# LIDAR-Lite-Shield-ArduinoUNO-StepperVers.net
KiCad netlist of a schematic drawn in EAGLE
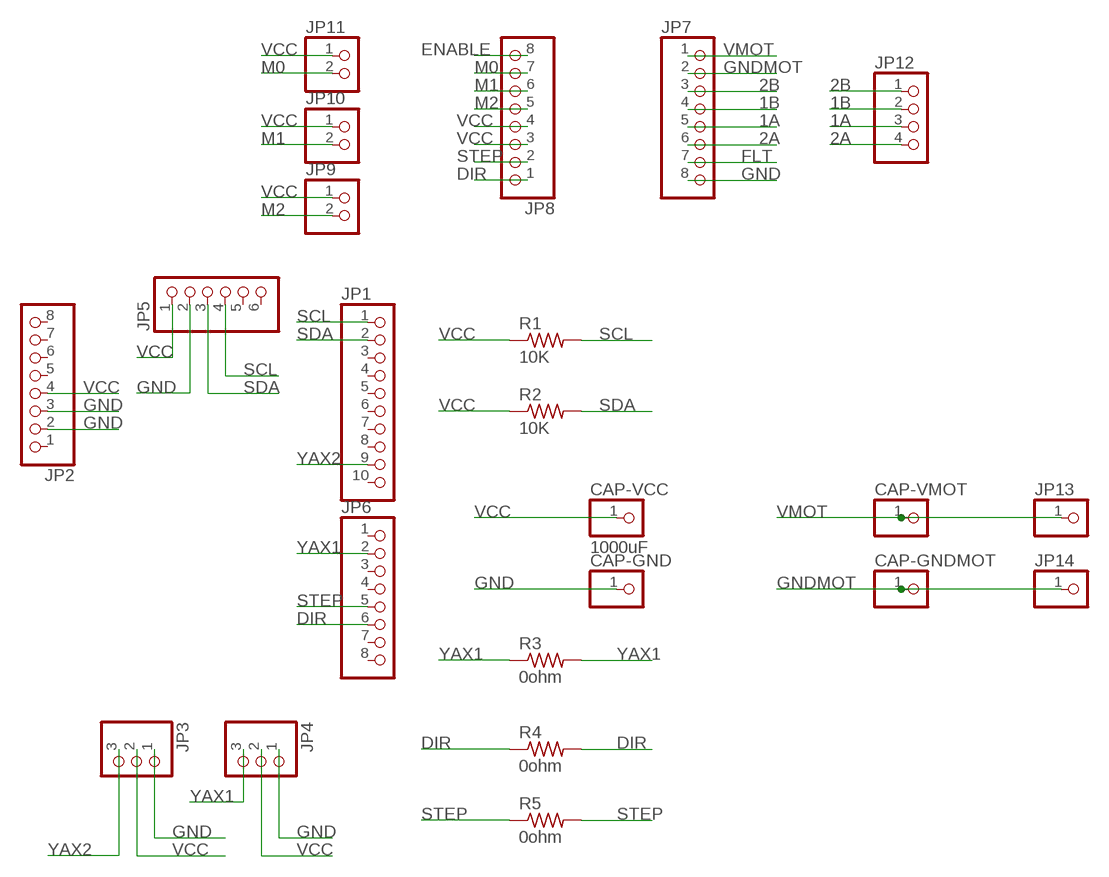
[diagram p0: schematic, sheet 1]

(export (version "E")
  (design (tool "Eeschema 10.0.6"))
  (components
    (comp (ref "CAP-GND")
      (value "PINHD-1X1")
      (footprint "eagle-import:1X01")
      (libsource (lib "eagle-import") (part "PINHD-1X1"))
    )
    (comp (ref "CAP-GNDMOT")
      (value "PINHD-1X1")
      (footprint "eagle-import:1X01")
      (libsource (lib "eagle-import") (part "PINHD-1X1"))
    )
    (comp (ref "CAP-VCC")
      (value "1000uF")
      (footprint "eagle-import:1X01")
      (libsource (lib "eagle-import") (part "PINHD-1X1"))
    )
    (comp (ref "CAP-VMOT")
      (value "PINHD-1X1")
      (footprint "eagle-import:1X01")
      (libsource (lib "eagle-import") (part "PINHD-1X1"))
    )
    (comp (ref "JP1")
      (value "PINHD-1X10")
      (footprint "eagle-import:1X10")
      (libsource (lib "eagle-import") (part "PINHD-1X10"))
    )
    (comp (ref "JP2")
      (value "PINHD-1X8")
      (footprint "eagle-import:1X08")
      (libsource (lib "eagle-import") (part "PINHD-1X8"))
    )
    (comp (ref "JP3")
      (value "PINHD-1X3")
      (footprint "eagle-import:1X03")
      (libsource (lib "eagle-import") (part "PINHD-1X3"))
    )
    (comp (ref "JP4")
      (value "PINHD-1X3")
      (footprint "eagle-import:1X03")
      (libsource (lib "eagle-import") (part "PINHD-1X3"))
    )
    (comp (ref "JP5")
      (value "PINHD-1X6")
      (footprint "eagle-import:1X06")
      (libsource (lib "eagle-import") (part "PINHD-1X6"))
    )
    (comp (ref "JP6")
      (value "PINHD-1X8")
      (footprint "eagle-import:1X08")
      (libsource (lib "eagle-import") (part "PINHD-1X8"))
    )
    (comp (ref "JP7")
      (value "PINHD-1X8")
      (footprint "eagle-import:1X08")
      (libsource (lib "eagle-import") (part "PINHD-1X8"))
    )
    (comp (ref "JP8")
      (value "PINHD-1X8")
      (footprint "eagle-import:1X08")
      (libsource (lib "eagle-import") (part "PINHD-1X8"))
    )
    (comp (ref "JP9")
      (value "PINHD-1X2")
      (footprint "eagle-import:1X02")
      (libsource (lib "eagle-import") (part "PINHD-1X2"))
    )
    (comp (ref "JP10")
      (value "PINHD-1X2")
      (footprint "eagle-import:1X02")
      (libsource (lib "eagle-import") (part "PINHD-1X2"))
    )
    (comp (ref "JP11")
      (value "PINHD-1X2")
      (footprint "eagle-import:1X02")
      (libsource (lib "eagle-import") (part "PINHD-1X2"))
    )
    (comp (ref "JP12")
      (value "PINHD-1X4")
      (footprint "eagle-import:1X04")
      (libsource (lib "eagle-import") (part "PINHD-1X4"))
    )
    (comp (ref "JP13")
      (value "PINHD-1X1")
      (footprint "eagle-import:1X01")
      (libsource (lib "eagle-import") (part "PINHD-1X1"))
    )
    (comp (ref "JP14")
      (value "PINHD-1X1")
      (footprint "eagle-import:1X01")
      (libsource (lib "eagle-import") (part "PINHD-1X1"))
    )
    (comp (ref "R1")
      (value "10K")
      (footprint "eagle-import:R1206FAB")
      (libsource (lib "eagle-import") (part "RES-US1206FAB"))
    )
    (comp (ref "R2")
      (value "10K")
      (footprint "eagle-import:R1206FAB")
      (libsource (lib "eagle-import") (part "RES-US1206FAB"))
    )
    (comp (ref "R3")
      (value "0ohm")
      (footprint "eagle-import:R1206FAB")
      (libsource (lib "eagle-import") (part "RES-US1206FAB"))
    )
    (comp (ref "R4")
      (value "0ohm")
      (footprint "eagle-import:R1206FAB")
      (libsource (lib "eagle-import") (part "RES-US1206FAB"))
    )
    (comp (ref "R5")
      (value "0ohm")
      (footprint "eagle-import:R1206FAB")
      (libsource (lib "eagle-import") (part "RES-US1206FAB"))
    )
  )
  (nets
    (net (code "1") (name "/1A") (class "Default")
      (node (ref "JP12") (pin "3") (pinfunction "3_3") (pintype "passive"))
      (node (ref "JP7") (pin "5") (pinfunction "5_5") (pintype "passive"))
    )
    (net (code "2") (name "/1B") (class "Default")
      (node (ref "JP12") (pin "2") (pinfunction "2_2") (pintype "passive"))
      (node (ref "JP7") (pin "4") (pinfunction "4_4") (pintype "passive"))
    )
    (net (code "3") (name "/2A") (class "Default")
      (node (ref "JP12") (pin "4") (pinfunction "4_4") (pintype "passive"))
      (node (ref "JP7") (pin "6") (pinfunction "6_6") (pintype "passive"))
    )
    (net (code "4") (name "/2B") (class "Default")
      (node (ref "JP12") (pin "1") (pinfunction "1_1") (pintype "passive"))
      (node (ref "JP7") (pin "3") (pinfunction "3_3") (pintype "passive"))
    )
    (net (code "5") (name "/DIR") (class "Default")
      (node (ref "JP6") (pin "6") (pinfunction "6_6") (pintype "passive"))
      (node (ref "JP8") (pin "1") (pinfunction "1_1") (pintype "passive"))
      (node (ref "R4") (pin "1") (pinfunction "1_1") (pintype "passive"))
      (node (ref "R4") (pin "2") (pinfunction "2_2") (pintype "passive"))
    )
    (net (code "6") (name "/ENABLE") (class "Default")
      (node (ref "JP8") (pin "8") (pinfunction "8_8") (pintype "passive"))
    )
    (net (code "7") (name "/FLT") (class "Default")
      (node (ref "JP7") (pin "7") (pinfunction "7_7") (pintype "passive"))
    )
    (net (code "8") (name "/GND") (class "Default")
      (node (ref "CAP-GND") (pin "1") (pinfunction "1_1") (pintype "passive"))
      (node (ref "JP2") (pin "2") (pinfunction "2_2") (pintype "passive"))
      (node (ref "JP2") (pin "3") (pinfunction "3_3") (pintype "passive"))
      (node (ref "JP3") (pin "1") (pinfunction "1_1") (pintype "passive"))
      (node (ref "JP4") (pin "1") (pinfunction "1_1") (pintype "passive"))
      (node (ref "JP5") (pin "2") (pinfunction "2_2") (pintype "passive"))
      (node (ref "JP7") (pin "8") (pinfunction "8_8") (pintype "passive"))
    )
    (net (code "9") (name "/GNDMOT") (class "Default")
      (node (ref "CAP-GNDMOT") (pin "1") (pinfunction "1_1") (pintype "passive"))
      (node (ref "JP14") (pin "1") (pinfunction "1_1") (pintype "passive"))
      (node (ref "JP7") (pin "2") (pinfunction "2_2") (pintype "passive"))
    )
    (net (code "10") (name "/M0") (class "Default")
      (node (ref "JP11") (pin "2") (pinfunction "2_2") (pintype "passive"))
      (node (ref "JP8") (pin "7") (pinfunction "7_7") (pintype "passive"))
    )
    (net (code "11") (name "/M1") (class "Default")
      (node (ref "JP10") (pin "2") (pinfunction "2_2") (pintype "passive"))
      (node (ref "JP8") (pin "6") (pinfunction "6_6") (pintype "passive"))
    )
    (net (code "12") (name "/M2") (class "Default")
      (node (ref "JP8") (pin "5") (pinfunction "5_5") (pintype "passive"))
      (node (ref "JP9") (pin "2") (pinfunction "2_2") (pintype "passive"))
    )
    (net (code "13") (name "/SCL") (class "Default")
      (node (ref "JP1") (pin "1") (pinfunction "1_1") (pintype "passive"))
      (node (ref "JP5") (pin "4") (pinfunction "4_4") (pintype "passive"))
      (node (ref "R1") (pin "2") (pinfunction "2_2") (pintype "passive"))
    )
    (net (code "14") (name "/SDA") (class "Default")
      (node (ref "JP1") (pin "2") (pinfunction "2_2") (pintype "passive"))
      (node (ref "JP5") (pin "3") (pinfunction "3_3") (pintype "passive"))
      (node (ref "R2") (pin "2") (pinfunction "2_2") (pintype "passive"))
    )
    (net (code "15") (name "/STEP") (class "Default")
      (node (ref "JP6") (pin "5") (pinfunction "5_5") (pintype "passive"))
      (node (ref "JP8") (pin "2") (pinfunction "2_2") (pintype "passive"))
      (node (ref "R5") (pin "1") (pinfunction "1_1") (pintype "passive"))
      (node (ref "R5") (pin "2") (pinfunction "2_2") (pintype "passive"))
    )
    (net (code "16") (name "/VCC") (class "Default")
      (node (ref "CAP-VCC") (pin "1") (pinfunction "1_1") (pintype "passive"))
      (node (ref "JP10") (pin "1") (pinfunction "1_1") (pintype "passive"))
      (node (ref "JP11") (pin "1") (pinfunction "1_1") (pintype "passive"))
      (node (ref "JP2") (pin "4") (pinfunction "4_4") (pintype "passive"))
      (node (ref "JP3") (pin "2") (pinfunction "2_2") (pintype "passive"))
      (node (ref "JP4") (pin "2") (pinfunction "2_2") (pintype "passive"))
      (node (ref "JP5") (pin "1") (pinfunction "1_1") (pintype "passive"))
      (node (ref "JP8") (pin "3") (pinfunction "3_3") (pintype "passive"))
      (node (ref "JP8") (pin "4") (pinfunction "4_4") (pintype "passive"))
      (node (ref "JP9") (pin "1") (pinfunction "1_1") (pintype "passive"))
      (node (ref "R1") (pin "1") (pinfunction "1_1") (pintype "passive"))
      (node (ref "R2") (pin "1") (pinfunction "1_1") (pintype "passive"))
    )
    (net (code "17") (name "/VMOT") (class "Default")
      (node (ref "CAP-VMOT") (pin "1") (pinfunction "1_1") (pintype "passive"))
      (node (ref "JP13") (pin "1") (pinfunction "1_1") (pintype "passive"))
      (node (ref "JP7") (pin "1") (pinfunction "1_1") (pintype "passive"))
    )
    (net (code "18") (name "/YAX1") (class "Default")
      (node (ref "JP4") (pin "3") (pinfunction "3_3") (pintype "passive"))
      (node (ref "JP6") (pin "2") (pinfunction "2_2") (pintype "passive"))
      (node (ref "R3") (pin "1") (pinfunction "1_1") (pintype "passive"))
      (node (ref "R3") (pin "2") (pinfunction "2_2") (pintype "passive"))
    )
    (net (code "19") (name "/YAX2") (class "Default")
      (node (ref "JP1") (pin "9") (pinfunction "9_9") (pintype "passive"))
      (node (ref "JP3") (pin "3") (pinfunction "3_3") (pintype "passive"))
    )
    (net (code "20") (name "unconnected-(JP1-Pad3)") (class "Default")
      (node (ref "JP1") (pin "3") (pinfunction "3_3") (pintype "passive"))
    )
    (net (code "21") (name "unconnected-(JP1-Pad4)") (class "Default")
      (node (ref "JP1") (pin "4") (pinfunction "4_4") (pintype "passive"))
    )
    (net (code "22") (name "unconnected-(JP1-Pad5)") (class "Default")
      (node (ref "JP1") (pin "5") (pinfunction "5_5") (pintype "passive"))
    )
    (net (code "23") (name "unconnected-(JP1-Pad6)") (class "Default")
      (node (ref "JP1") (pin "6") (pinfunction "6_6") (pintype "passive"))
    )
    (net (code "24") (name "unconnected-(JP1-Pad7)") (class "Default")
      (node (ref "JP1") (pin "7") (pinfunction "7_7") (pintype "passive"))
    )
    (net (code "25") (name "unconnected-(JP1-Pad8)") (class "Default")
      (node (ref "JP1") (pin "8") (pinfunction "8_8") (pintype "passive"))
    )
    (net (code "26") (name "unconnected-(JP1-Pad10)") (class "Default")
      (node (ref "JP1") (pin "10") (pinfunction "10_10") (pintype "passive"))
    )
    (net (code "27") (name "unconnected-(JP2-Pad1)") (class "Default")
      (node (ref "JP2") (pin "1") (pinfunction "1_1") (pintype "passive"))
    )
    (net (code "28") (name "unconnected-(JP2-Pad5)") (class "Default")
      (node (ref "JP2") (pin "5") (pinfunction "5_5") (pintype "passive"))
    )
    (net (code "29") (name "unconnected-(JP2-Pad6)") (class "Default")
      (node (ref "JP2") (pin "6") (pinfunction "6_6") (pintype "passive"))
    )
    (net (code "30") (name "unconnected-(JP2-Pad7)") (class "Default")
      (node (ref "JP2") (pin "7") (pinfunction "7_7") (pintype "passive"))
    )
    (net (code "31") (name "unconnected-(JP2-Pad8)") (class "Default")
      (node (ref "JP2") (pin "8") (pinfunction "8_8") (pintype "passive"))
    )
    (net (code "32") (name "unconnected-(JP5-Pad5)") (class "Default")
      (node (ref "JP5") (pin "5") (pinfunction "5_5") (pintype "passive"))
    )
    (net (code "33") (name "unconnected-(JP5-Pad6)") (class "Default")
      (node (ref "JP5") (pin "6") (pinfunction "6_6") (pintype "passive"))
    )
    (net (code "34") (name "unconnected-(JP6-Pad1)") (class "Default")
      (node (ref "JP6") (pin "1") (pinfunction "1_1") (pintype "passive"))
    )
    (net (code "35") (name "unconnected-(JP6-Pad3)") (class "Default")
      (node (ref "JP6") (pin "3") (pinfunction "3_3") (pintype "passive"))
    )
    (net (code "36") (name "unconnected-(JP6-Pad4)") (class "Default")
      (node (ref "JP6") (pin "4") (pinfunction "4_4") (pintype "passive"))
    )
    (net (code "37") (name "unconnected-(JP6-Pad7)") (class "Default")
      (node (ref "JP6") (pin "7") (pinfunction "7_7") (pintype "passive"))
    )
    (net (code "38") (name "unconnected-(JP6-Pad8)") (class "Default")
      (node (ref "JP6") (pin "8") (pinfunction "8_8") (pintype "passive"))
    )
  )
)
